# circuit_de_boost.net
KiCad netlist of a schematic drawn in Altium Designer
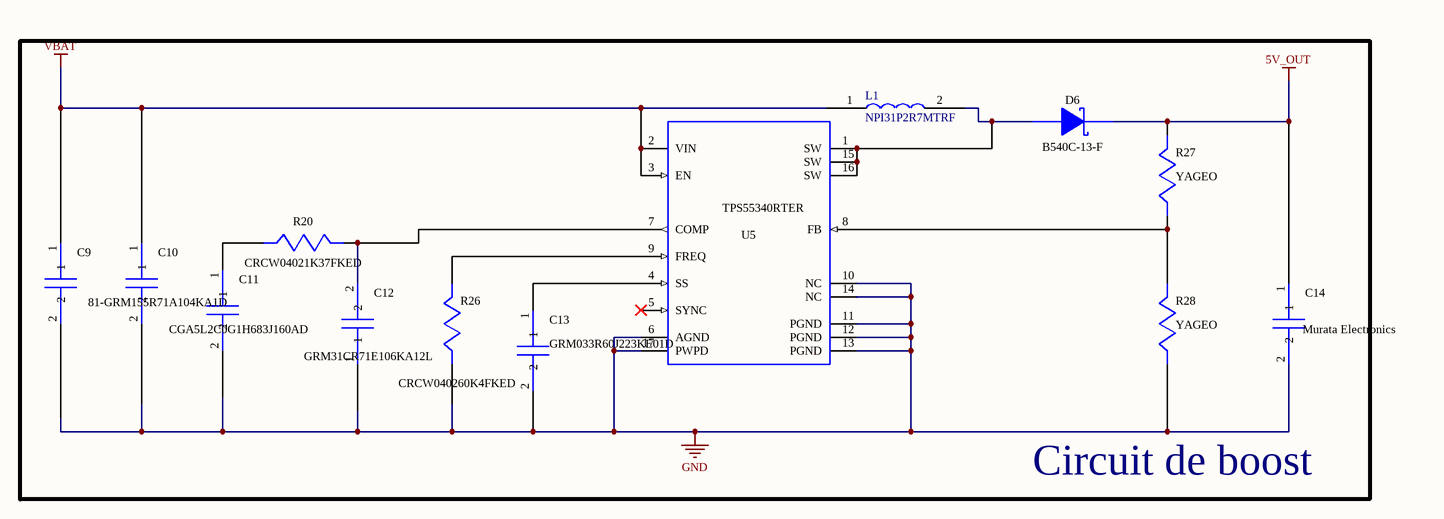
[diagram p0: circuit de boost.schdoc]

(export (version "E")
  (design (tool "Eeschema 10.0.6"))
  (components
    (comp (ref "C9")
      (value "GRM31CR71E106KA12L")
      (footprint "GRM31CR71E106KA12L")
      (description "Multilayer Ceramic Capacitors MLCC - SMD/SMT 10 uF 25 VDC 10% 1206 X7R")
      (fields (field (name "MFR") "MuRata"))
      (libsource (lib "TI WEBENCH") (part "Cin"))
    )
    (comp (ref "C10")
      (value "GRM155R71A104KA01D")
      (footprint "GRM155R71A104KA01D")
      (description "Multilayer Ceramic Capacitors MLCC - SMD/SMT 0.1 uF 10 VDC 10% 0402 X7R")
      (fields (field (name "MFR") "Murata") (field (name "SUPPLIER RÉF") "81-GRM155R71A104KA1D"))
      (libsource (lib "TI WEBENCH") (part "Cinx"))
    )
    (comp (ref "C11")
      (value "CGA5L2C0G1H683J160AD")
      (footprint "CGA5L2C0G1H683J160AD")
      (description "Multilayer Ceramic Capacitors MLCC - SMD/SMT 1206 50V 0.068uF C0G 5% AEC-Q200 EPXY")
      (fields (field (name "MFR") "TDK") (field (name "MFR RÉF") "CGA5L2C0G1H683J160AD"))
      (libsource (lib "TI WEBENCH") (part "Ccomp"))
    )
    (comp (ref "C12")
      (value "GRM2195C1H152JA01D")
      (footprint "GRM2195C1H152JA01L")
      (description "Multilayer Ceramic Capacitors MLCC - SMD/SMT 10 uF 25 VDC 10% 1206 X7R")
      (fields (field (name "MFR") "MuRata") (field (name "MFR RÉF") "GRM31CR71E106KA12L"))
      (libsource (lib "TI WEBENCH") (part "Ccomp2"))
    )
    (comp (ref "C13")
      (value "GRM033R60J223KE01D")
      (footprint "GRM033R60J223KE01D")
      (description "Multilayer Ceramic Capacitors MLCC - SMD/SMT 0.022 uF 6.3 VDC 10% 0201 X5R")
      (fields (field (name "MFR") "MuRata") (field (name "MFR RÉF") "GRM033R60J223KE01D"))
      (libsource (lib "TI WEBENCH") (part "Css"))
    )
    (comp (ref "C14")
      (value "GRM32EC80J107ME20L")
      (footprint "GRM32EC80J107ME20L")
      (description "Multilayer Ceramic Capacitors MLCC - SMD/SMT 100 uF 6.3 VDC 20% 1210 X6S")
      (fields (field (name "MFR") "Murata Electronics"))
      (libsource (lib "TI WEBENCH") (part "Cout"))
    )
    (comp (ref "D6")
      (value "B540C-13-F")
      (footprint "B540C-13-F")
      (description "Schottky Diodes & Rectifiers 40V 5A")
      (fields (field (name "MFR") "Diodes Incorporated") (field (name "MFR RÉF") "B540C-13-F"))
      (libsource (lib "TI WEBENCH") (part "D1"))
    )
    (comp (ref "L1")
      (value "NPI31P2R7MTRF")
      (footprint "NPI31P2R7MTRF")
      (description "Power Inductor (SMD), 2.7 uH, ± 20%, 6.6 A, Unshielded, 7 A, 13.2mm x 9.9mm x 6.4mm")
      (fields (field (name "MFR") "NIC"))
      (libsource (lib "Data_logger") (part "NPI31P2R7MTRF"))
    )
    (comp (ref "R20")
      (value "CRCW04021K37FKED")
      (footprint "CRCW04021K37FKED")
      (description "Thick Film Resistors - SMD 1/16watt 1.37Kohms 1%")
      (fields (field (name "MFR") "Vishay Dale") (field (name "MFR RÉF") "CRCW04021K37FKED"))
      (libsource (lib "TI WEBENCH") (part "Rcomp"))
    )
    (comp (ref "R26")
      (value "CRCW040260K4FKED")
      (footprint "CRCW040260K4FKED")
      (description "Thick Film Resistors - SMD 1/16watt 60.4Kohms 1%")
      (fields (field (name "MFR") "Vishay-Dale") (field (name "MFR RÉF") "CRCW040260K4FKED"))
      (libsource (lib "TI WEBENCH") (part "Rt"))
    )
    (comp (ref "R27")
      (value "RT0805BRD0730K5L")
      (footprint "RT0805BRD0730K5L")
      (description "Thin Film Resistors - SMD 1/8W 30.5K Ohms 0.1%")
      (fields (field (name "MFR") "YAGEO"))
      (libsource (lib "TI WEBENCH") (part "Rfbt"))
    )
    (comp (ref "R28")
      (value "RC0201FR-0710KL")
      (footprint "RC0201FR-0710KL")
      (description "Thick Film Resistors - SMD 10 kOhms 50mW 0201 1%")
      (fields (field (name "MFR") "YAGEO"))
      (libsource (lib "TI WEBENCH") (part "Rfbb"))
    )
    (comp (ref "U5")
      (value "TPS55340RTER")
      (footprint "TPS55340RTER")
      (description "Switching Voltage Regulators 5A 40V Wide In Range DC-DC Converter")
      (fields (field (name "MFR") "Texas Instruments"))
      (libsource (lib "TI WEBENCH") (part "U1"))
    )
  )
  (nets
    (net (code "1") (name "5V_OUT") (class "Default")
      (node (ref "C14") (pin "1") (pinfunction "1_1") (pintype "passive"))
      (node (ref "D6") (pin "1") (pinfunction "K_1") (pintype "passive"))
      (node (ref "R27") (pin "1") (pinfunction "1_1") (pintype "passive"))
    )
    (net (code "2") (name "GND") (class "Default")
      (node (ref "C10") (pin "2") (pinfunction "2_2") (pintype "passive"))
      (node (ref "C11") (pin "2") (pinfunction "2_2") (pintype "passive"))
      (node (ref "C12") (pin "1") (pinfunction "1_1") (pintype "passive"))
      (node (ref "C13") (pin "2") (pinfunction "2_2") (pintype "passive"))
      (node (ref "C14") (pin "2") (pinfunction "2_2") (pintype "passive"))
      (node (ref "C9") (pin "2") (pinfunction "2_2") (pintype "passive"))
      (node (ref "R26") (pin "2") (pinfunction "2_2") (pintype "passive"))
      (node (ref "R28") (pin "2") (pinfunction "2_2") (pintype "passive"))
      (node (ref "U5") (pin "10") (pinfunction "NC_10") (pintype "passive"))
      (node (ref "U5") (pin "11") (pinfunction "PGND_11") (pintype "power_in"))
      (node (ref "U5") (pin "12") (pinfunction "PGND_12") (pintype "power_in"))
      (node (ref "U5") (pin "13") (pinfunction "PGND_13") (pintype "power_in"))
      (node (ref "U5") (pin "14") (pinfunction "NC_14") (pintype "passive"))
      (node (ref "U5") (pin "17") (pinfunction "PWPD_17") (pintype "power_in"))
      (node (ref "U5") (pin "6") (pinfunction "AGND_6") (pintype "power_in"))
    )
    (net (code "3") (name "Net-(C11-Pad1)") (class "Default")
      (node (ref "C11") (pin "1") (pinfunction "1_1") (pintype "passive"))
      (node (ref "R20") (pin "2") (pinfunction "2_2") (pintype "passive"))
    )
    (net (code "4") (name "Net-(D6-A)") (class "Default")
      (node (ref "D6") (pin "2") (pinfunction "A_2") (pintype "passive"))
      (node (ref "L1") (pin "2") (pintype "passive"))
      (node (ref "U5") (pin "1") (pinfunction "SW_1") (pintype "power_in"))
      (node (ref "U5") (pin "15") (pinfunction "SW_15") (pintype "power_in"))
      (node (ref "U5") (pin "16") (pinfunction "SW_16") (pintype "power_in"))
    )
    (net (code "5") (name "Net-(U5-COMP)") (class "Default")
      (node (ref "C12") (pin "2") (pinfunction "2_2") (pintype "passive"))
      (node (ref "R20") (pin "1") (pinfunction "1_1") (pintype "passive"))
      (node (ref "U5") (pin "7") (pinfunction "COMP_7") (pintype "output"))
    )
    (net (code "6") (name "Net-(U5-FB)") (class "Default")
      (node (ref "R27") (pin "2") (pinfunction "2_2") (pintype "passive"))
      (node (ref "R28") (pin "1") (pinfunction "1_1") (pintype "passive"))
      (node (ref "U5") (pin "8") (pinfunction "FB_8") (pintype "input"))
    )
    (net (code "7") (name "Net-(U5-FREQ)") (class "Default")
      (node (ref "R26") (pin "1") (pinfunction "1_1") (pintype "passive"))
      (node (ref "U5") (pin "9") (pinfunction "FREQ_9") (pintype "input"))
    )
    (net (code "8") (name "Net-(U5-SS)") (class "Default")
      (node (ref "C13") (pin "1") (pinfunction "1_1") (pintype "passive"))
      (node (ref "U5") (pin "4") (pinfunction "SS_4") (pintype "input"))
    )
    (net (code "9") (name "VBAT") (class "Default")
      (node (ref "C10") (pin "1") (pinfunction "1_1") (pintype "passive"))
      (node (ref "C9") (pin "1") (pinfunction "1_1") (pintype "passive"))
      (node (ref "L1") (pin "1") (pintype "passive"))
      (node (ref "U5") (pin "2") (pinfunction "VIN_2") (pintype "power_in"))
      (node (ref "U5") (pin "3") (pinfunction "EN_3") (pintype "input"))
    )
    (net (code "10") (name "unconnected-(U5-SYNC-Pad5)") (class "Default")
      (node (ref "U5") (pin "5") (pinfunction "SYNC_5") (pintype "input+no_connect"))
    )
  )
)
